# Relay.net
KiCad netlist of a schematic drawn in Altium Designer
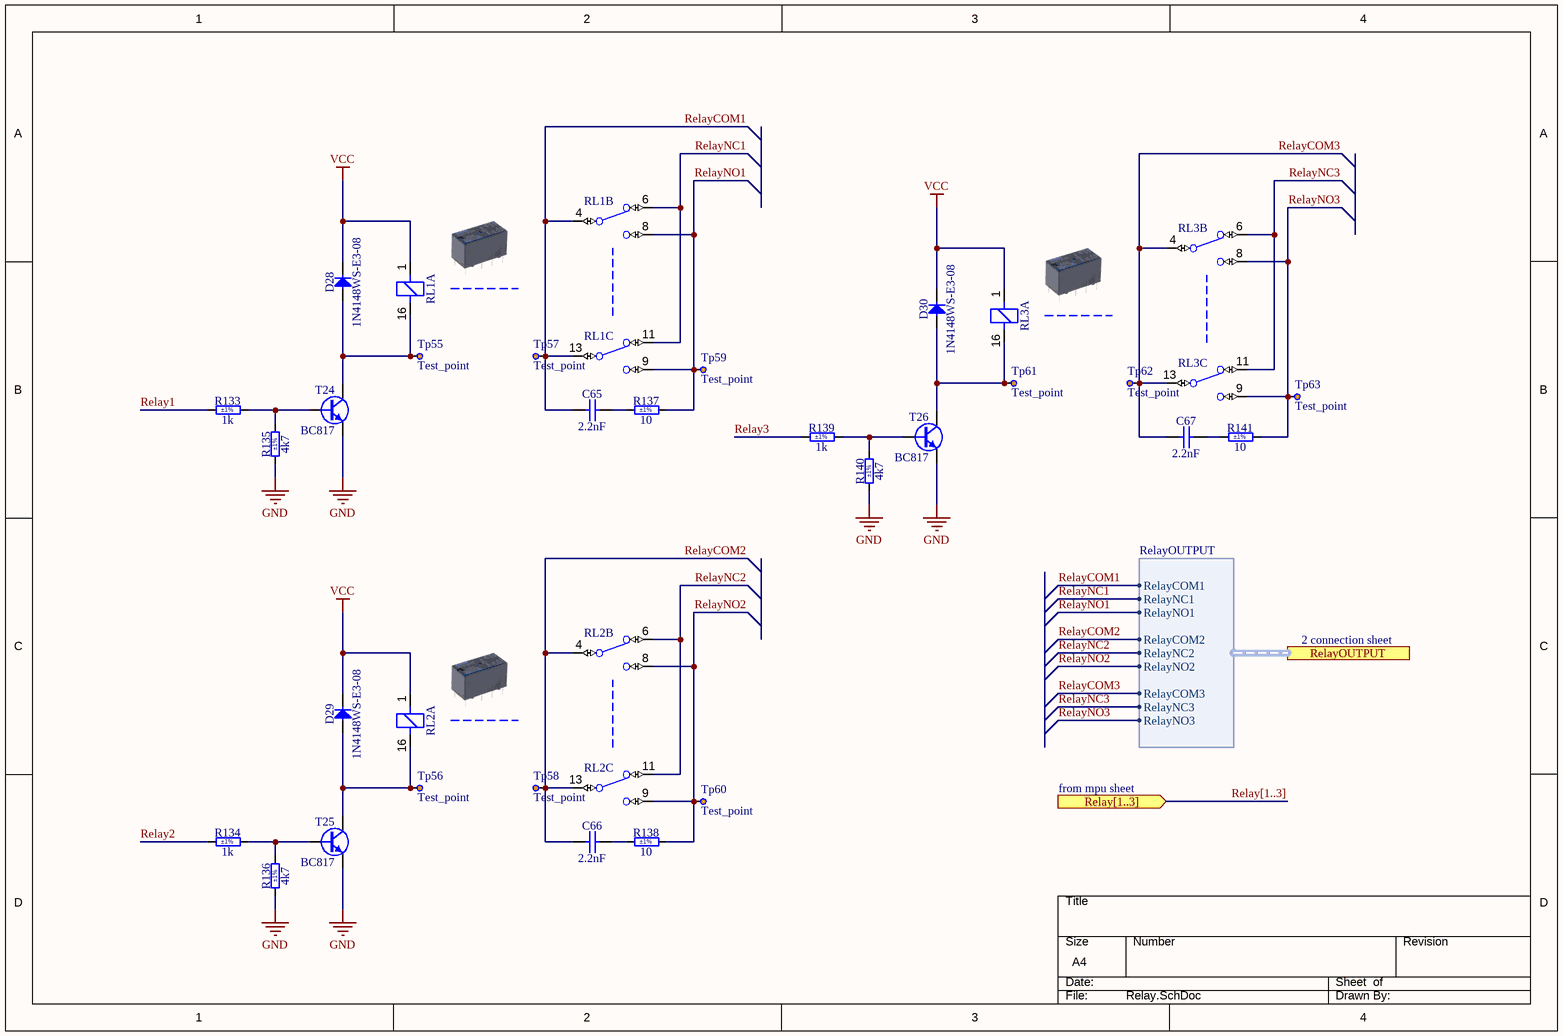
[diagram p0: Relay.SchDoc]

(export (version "E")
  (design (tool "Eeschema 10.0.6"))
  (components
    (comp (ref "C65")
      (value "2.2nF")
      (footprint "CAPRB_MURATA_DE2E3KY222MA2BM01F")
      (description "Non-polarised capacitor")
      (fields
        (field (name "PART NUMBER") "CCR_2.2NF_250V_20%_MURATA_DE2E3KY222MA2BM01F")
        (field (name "VOLTAGE") "250VAC")
        (field (name "AUTHOR") "CERN DEM JLC")
      )
      (libsource (lib "Capacitors") (part "Capacitor - non polarized"))
    )
    (comp (ref "C66")
      (value "2.2nF")
      (footprint "CAPRB_MURATA_DE2E3KY222MA2BM01F")
      (description "Non-polarised capacitor")
      (fields
        (field (name "PART NUMBER") "CCR_2.2NF_250V_20%_MURATA_DE2E3KY222MA2BM01F")
        (field (name "VOLTAGE") "250VAC")
        (field (name "AUTHOR") "CERN DEM JLC")
      )
      (libsource (lib "Capacitors") (part "Capacitor - non polarized"))
    )
    (comp (ref "C67")
      (value "2.2nF")
      (footprint "CAPRB_MURATA_DE2E3KY222MA2BM01F")
      (description "Non-polarised capacitor")
      (fields
        (field (name "PART NUMBER") "CCR_2.2NF_250V_20%_MURATA_DE2E3KY222MA2BM01F")
        (field (name "VOLTAGE") "250VAC")
        (field (name "AUTHOR") "CERN DEM JLC")
      )
      (libsource (lib "Capacitors") (part "Capacitor - non polarized"))
    )
    (comp (ref "D28")
      (value "1N4148WS-E3-08")
      (footprint "SOD2713X115N")
      (description "Diode")
      (fields
        (field (name "VOLTAGE") "75V")
        (field (name "POWER") "150mA")
        (field (name "AUTHOR") "CERN DEM JLC")
      )
      (libsource (lib "ICs And Semiconductors") (part "Diode"))
    )
    (comp (ref "D29")
      (value "1N4148WS-E3-08")
      (footprint "SOD2713X115N")
      (description "Diode")
      (fields
        (field (name "VOLTAGE") "75V")
        (field (name "POWER") "150mA")
        (field (name "AUTHOR") "CERN DEM JLC")
      )
      (libsource (lib "ICs And Semiconductors") (part "Diode"))
    )
    (comp (ref "D30")
      (value "1N4148WS-E3-08")
      (footprint "SOD2713X115N")
      (description "Diode")
      (fields
        (field (name "VOLTAGE") "75V")
        (field (name "POWER") "150mA")
        (field (name "AUTHOR") "CERN DEM JLC")
      )
      (libsource (lib "ICs And Semiconductors") (part "Diode"))
    )
    (comp (ref "R133")
      (value "1k")
      (footprint "RESC1608X55N")
      (description "Resistor - 1%")
      (fields
        (field (name "TOLERANCE") "±1%")
        (field (name "PART NUMBER") "R0603_1K_1%_0.1W_100PPM")
        (field (name "POWER") "0.1W")
        (field (name "AUTHOR") "CERN DEM JLC")
      )
      (libsource (lib "Resistors") (part "Resistor - 1%"))
    )
    (comp (ref "R134")
      (value "1k")
      (footprint "RESC1608X55N")
      (description "Resistor - 1%")
      (fields
        (field (name "TOLERANCE") "±1%")
        (field (name "PART NUMBER") "R0603_1K_1%_0.1W_100PPM")
        (field (name "POWER") "0.1W")
        (field (name "AUTHOR") "CERN DEM JLC")
      )
      (libsource (lib "Resistors") (part "Resistor - 1%"))
    )
    (comp (ref "R135")
      (value "4k7")
      (footprint "RESC1608X55N")
      (description "Resistor - 1%")
      (fields
        (field (name "TOLERANCE") "±1%")
        (field (name "PART NUMBER") "R0603_4K7_1%_0.1W_100PPM")
        (field (name "POWER") "0.1W")
        (field (name "AUTHOR") "CERN DEM JLC")
      )
      (libsource (lib "Resistors") (part "Resistor - 1%"))
    )
    (comp (ref "R136")
      (value "4k7")
      (footprint "RESC1608X55N")
      (description "Resistor - 1%")
      (fields
        (field (name "TOLERANCE") "±1%")
        (field (name "PART NUMBER") "R0603_4K7_1%_0.1W_100PPM")
        (field (name "POWER") "0.1W")
        (field (name "AUTHOR") "CERN DEM JLC")
      )
      (libsource (lib "Resistors") (part "Resistor - 1%"))
    )
    (comp (ref "R137")
      (value "10")
      (footprint "RESC3216X65N")
      (description "Resistor - 1%")
      (fields
        (field (name "TOLERANCE") "±1%")
        (field (name "PART NUMBER") "R1206_10R_1%_0.25W_100PPM")
        (field (name "POWER") "0.25W")
        (field (name "AUTHOR") "CERN DEM BC")
      )
      (libsource (lib "Resistors") (part "Resistor - 1%"))
    )
    (comp (ref "R138")
      (value "10")
      (footprint "RESC3216X65N")
      (description "Resistor - 1%")
      (fields
        (field (name "TOLERANCE") "±1%")
        (field (name "PART NUMBER") "R1206_10R_1%_0.25W_100PPM")
        (field (name "POWER") "0.25W")
        (field (name "AUTHOR") "CERN DEM BC")
      )
      (libsource (lib "Resistors") (part "Resistor - 1%"))
    )
    (comp (ref "R139")
      (value "1k")
      (footprint "RESC1608X55N")
      (description "Resistor - 1%")
      (fields
        (field (name "TOLERANCE") "±1%")
        (field (name "PART NUMBER") "R0603_1K_1%_0.1W_100PPM")
        (field (name "POWER") "0.1W")
        (field (name "AUTHOR") "CERN DEM JLC")
      )
      (libsource (lib "Resistors") (part "Resistor - 1%"))
    )
    (comp (ref "R140")
      (value "4k7")
      (footprint "RESC1608X55N")
      (description "Resistor - 1%")
      (fields
        (field (name "TOLERANCE") "±1%")
        (field (name "PART NUMBER") "R0603_4K7_1%_0.1W_100PPM")
        (field (name "POWER") "0.1W")
        (field (name "AUTHOR") "CERN DEM JLC")
      )
      (libsource (lib "Resistors") (part "Resistor - 1%"))
    )
    (comp (ref "R141")
      (value "10")
      (footprint "RESC3216X65N")
      (description "Resistor - 1%")
      (fields
        (field (name "TOLERANCE") "±1%")
        (field (name "PART NUMBER") "R1206_10R_1%_0.25W_100PPM")
        (field (name "POWER") "0.25W")
        (field (name "AUTHOR") "CERN DEM BC")
      )
      (libsource (lib "Resistors") (part "Resistor - 1%"))
    )
    (comp (ref "RL1")
      (value "REL_OMRON_G5V-2")
      (footprint "REL_OMRON_G5V-2")
      (description "Miniature Relay for Signal Circuits")
      (fields
        (field (name "PART NUMBER") "REL_OMRON_G5V-2-H1 24VDC")
        (field (name "MANUFACTURER") "OMRON ELECTRONIC")
        (field (name "AUTHOR") "CERN DEM JLC")
      )
      (libsource (lib "Eletro-mechanical") (part "REL_OMRON_G5V-2"))
    )
    (comp (ref "RL2")
      (value "REL_OMRON_G5V-2")
      (footprint "REL_OMRON_G5V-2")
      (description "Miniature Relay for Signal Circuits")
      (fields
        (field (name "PART NUMBER") "REL_OMRON_G5V-2-H1 24VDC")
        (field (name "MANUFACTURER") "OMRON ELECTRONIC")
        (field (name "AUTHOR") "CERN DEM JLC")
      )
      (libsource (lib "") (part "REL_OMRON_G5V-2_1"))
    )
    (comp (ref "RL3")
      (value "REL_OMRON_G5V-2")
      (footprint "REL_OMRON_G5V-2")
      (description "Miniature Relay for Signal Circuits")
      (fields
        (field (name "PART NUMBER") "REL_OMRON_G5V-2-H1 24VDC")
        (field (name "MANUFACTURER") "OMRON ELECTRONIC")
        (field (name "AUTHOR") "CERN DEM JLC")
      )
      (libsource (lib "Eletro-mechanical") (part "REL_OMRON_G5V-2"))
    )
    (comp (ref "T24")
      (value "BC817")
      (footprint "SOT95P230X110-3N")
      (description "NPN Transistor")
      (fields (field (name "MANUFACTURER") "NXP SEMICONDUCTORS") (field (name "AUTHOR") "CERN DEM JLC"))
      (libsource (lib "ICs And Semiconductors") (part "NPN B1 E2 C3"))
    )
    (comp (ref "T25")
      (value "BC817")
      (footprint "SOT95P230X110-3N")
      (description "NPN Transistor")
      (fields (field (name "MANUFACTURER") "NXP SEMICONDUCTORS") (field (name "AUTHOR") "CERN DEM JLC"))
      (libsource (lib "ICs And Semiconductors") (part "NPN B1 E2 C3"))
    )
    (comp (ref "T26")
      (value "BC817")
      (footprint "SOT95P230X110-3N")
      (description "NPN Transistor")
      (fields (field (name "MANUFACTURER") "NXP SEMICONDUCTORS") (field (name "AUTHOR") "CERN DEM JLC"))
      (libsource (lib "ICs And Semiconductors") (part "NPN B1 E2 C3"))
    )
    (comp (ref "Tp55")
      (value "Test_point")
      (footprint "fromST:TP_C40")
      (description "Test point")
      (fields (field (name "PUBLISHER") "Altium Limited"))
      (libsource (lib "Sajad_Altium_Library") (part "Test point"))
    )
    (comp (ref "Tp56")
      (value "Test_point")
      (footprint "fromST:TP_C40")
      (description "Test point")
      (fields (field (name "PUBLISHER") "Altium Limited"))
      (libsource (lib "Sajad_Altium_Library") (part "Test point"))
    )
    (comp (ref "Tp57")
      (value "Test_point")
      (footprint "fromST:TP_C40")
      (description "Test point")
      (fields (field (name "PUBLISHER") "Altium Limited"))
      (libsource (lib "Sajad_Altium_Library") (part "Test point"))
    )
    (comp (ref "Tp58")
      (value "Test_point")
      (footprint "fromST:TP_C40")
      (description "Test point")
      (fields (field (name "PUBLISHER") "Altium Limited"))
      (libsource (lib "Sajad_Altium_Library") (part "Test point"))
    )
    (comp (ref "Tp59")
      (value "Test_point")
      (footprint "fromST:TP_C40")
      (description "Test point")
      (fields (field (name "PUBLISHER") "Altium Limited"))
      (libsource (lib "Sajad_Altium_Library") (part "Test point"))
    )
    (comp (ref "Tp60")
      (value "Test_point")
      (footprint "fromST:TP_C40")
      (description "Test point")
      (fields (field (name "PUBLISHER") "Altium Limited"))
      (libsource (lib "Sajad_Altium_Library") (part "Test point"))
    )
    (comp (ref "Tp61")
      (value "Test_point")
      (footprint "fromST:TP_C40")
      (description "Test point")
      (fields (field (name "PUBLISHER") "Altium Limited"))
      (libsource (lib "Sajad_Altium_Library") (part "Test point"))
    )
    (comp (ref "Tp62")
      (value "Test_point")
      (footprint "fromST:TP_C40")
      (description "Test point")
      (fields (field (name "PUBLISHER") "Altium Limited"))
      (libsource (lib "Sajad_Altium_Library") (part "Test point"))
    )
    (comp (ref "Tp63")
      (value "Test_point")
      (footprint "fromST:TP_C40")
      (description "Test point")
      (fields (field (name "PUBLISHER") "Altium Limited"))
      (libsource (lib "Sajad_Altium_Library") (part "Test point"))
    )
  )
  (nets
    (net (code "2") (name "/Relay1") (class "Default")
      (node (ref "R133") (pin "1") (pinfunction "1_1") (pintype "passive"))
    )
    (net (code "3") (name "/Relay2") (class "Default")
      (node (ref "R134") (pin "1") (pinfunction "1_1") (pintype "passive"))
    )
    (net (code "4") (name "/Relay3") (class "Default")
      (node (ref "R139") (pin "1") (pinfunction "1_1") (pintype "passive"))
    )
    (net (code "5") (name "/RelayCOM1") (class "Default")
      (node (ref "C65") (pin "1") (pinfunction "1_1") (pintype "passive"))
      (node (ref "RL1") (pin "13") (pinfunction "C_13") (pintype "bidirectional"))
      (node (ref "RL1") (pin "4") (pinfunction "C_4") (pintype "bidirectional"))
      (node (ref "Tp57") (pin "1") (pinfunction "1_1") (pintype "passive"))
    )
    (net (code "6") (name "/RelayCOM2") (class "Default")
      (node (ref "C66") (pin "1") (pinfunction "1_1") (pintype "passive"))
      (node (ref "RL2") (pin "13") (pinfunction "C_13") (pintype "bidirectional"))
      (node (ref "RL2") (pin "4") (pinfunction "C_4") (pintype "bidirectional"))
      (node (ref "Tp58") (pin "1") (pinfunction "1_1") (pintype "passive"))
    )
    (net (code "7") (name "/RelayCOM3") (class "Default")
      (node (ref "C67") (pin "1") (pinfunction "1_1") (pintype "passive"))
      (node (ref "RL3") (pin "13") (pinfunction "C_13") (pintype "bidirectional"))
      (node (ref "RL3") (pin "4") (pinfunction "C_4") (pintype "bidirectional"))
      (node (ref "Tp62") (pin "1") (pinfunction "1_1") (pintype "passive"))
    )
    (net (code "8") (name "/RelayNC1") (class "Default")
      (node (ref "RL1") (pin "11") (pinfunction "NC_11") (pintype "bidirectional"))
      (node (ref "RL1") (pin "6") (pinfunction "NC_6") (pintype "bidirectional"))
    )
    (net (code "9") (name "/RelayNC2") (class "Default")
      (node (ref "RL2") (pin "11") (pinfunction "NC_11") (pintype "bidirectional"))
      (node (ref "RL2") (pin "6") (pinfunction "NC_6") (pintype "bidirectional"))
    )
    (net (code "10") (name "/RelayNC3") (class "Default")
      (node (ref "RL3") (pin "11") (pinfunction "NC_11") (pintype "bidirectional"))
      (node (ref "RL3") (pin "6") (pinfunction "NC_6") (pintype "bidirectional"))
    )
    (net (code "11") (name "/RelayNO1") (class "Default")
      (node (ref "R137") (pin "2") (pinfunction "2_2") (pintype "passive"))
      (node (ref "RL1") (pin "8") (pinfunction "NO_8") (pintype "bidirectional"))
      (node (ref "RL1") (pin "9") (pinfunction "NO_9") (pintype "bidirectional"))
      (node (ref "Tp59") (pin "1") (pinfunction "1_1") (pintype "passive"))
    )
    (net (code "12") (name "/RelayNO2") (class "Default")
      (node (ref "R138") (pin "2") (pinfunction "2_2") (pintype "passive"))
      (node (ref "RL2") (pin "8") (pinfunction "NO_8") (pintype "bidirectional"))
      (node (ref "RL2") (pin "9") (pinfunction "NO_9") (pintype "bidirectional"))
      (node (ref "Tp60") (pin "1") (pinfunction "1_1") (pintype "passive"))
    )
    (net (code "13") (name "/RelayNO3") (class "Default")
      (node (ref "R141") (pin "2") (pinfunction "2_2") (pintype "passive"))
      (node (ref "RL3") (pin "8") (pinfunction "NO_8") (pintype "bidirectional"))
      (node (ref "RL3") (pin "9") (pinfunction "NO_9") (pintype "bidirectional"))
      (node (ref "Tp63") (pin "1") (pinfunction "1_1") (pintype "passive"))
    )
    (net (code "16") (name "GND") (class "Default")
      (node (ref "R135") (pin "1") (pinfunction "1_1") (pintype "passive"))
      (node (ref "R136") (pin "1") (pinfunction "1_1") (pintype "passive"))
      (node (ref "R140") (pin "1") (pinfunction "1_1") (pintype "passive"))
      (node (ref "T24") (pin "2") (pinfunction "E_2") (pintype "passive"))
      (node (ref "T25") (pin "2") (pinfunction "E_2") (pintype "passive"))
      (node (ref "T26") (pin "2") (pinfunction "E_2") (pintype "passive"))
    )
    (net (code "17") (name "Net-(C65-Pad2)") (class "Default")
      (node (ref "C65") (pin "2") (pinfunction "2_2") (pintype "passive"))
      (node (ref "R137") (pin "1") (pinfunction "1_1") (pintype "passive"))
    )
    (net (code "18") (name "Net-(C66-Pad2)") (class "Default")
      (node (ref "C66") (pin "2") (pinfunction "2_2") (pintype "passive"))
      (node (ref "R138") (pin "1") (pinfunction "1_1") (pintype "passive"))
    )
    (net (code "19") (name "Net-(C67-Pad2)") (class "Default")
      (node (ref "C67") (pin "2") (pinfunction "2_2") (pintype "passive"))
      (node (ref "R141") (pin "1") (pinfunction "1_1") (pintype "passive"))
    )
    (net (code "20") (name "Net-(D28-A)") (class "Default")
      (node (ref "D28") (pin "2") (pinfunction "A_2") (pintype "passive"))
      (node (ref "RL1") (pin "16") (pinfunction "16_16") (pintype "passive"))
      (node (ref "T24") (pin "3") (pinfunction "C_3") (pintype "passive"))
      (node (ref "Tp55") (pin "1") (pinfunction "1_1") (pintype "passive"))
    )
    (net (code "21") (name "Net-(D29-A)") (class "Default")
      (node (ref "D29") (pin "2") (pinfunction "A_2") (pintype "passive"))
      (node (ref "RL2") (pin "16") (pinfunction "16_16") (pintype "passive"))
      (node (ref "T25") (pin "3") (pinfunction "C_3") (pintype "passive"))
      (node (ref "Tp56") (pin "1") (pinfunction "1_1") (pintype "passive"))
    )
    (net (code "22") (name "Net-(D30-A)") (class "Default")
      (node (ref "D30") (pin "2") (pinfunction "A_2") (pintype "passive"))
      (node (ref "RL3") (pin "16") (pinfunction "16_16") (pintype "passive"))
      (node (ref "T26") (pin "3") (pinfunction "C_3") (pintype "passive"))
      (node (ref "Tp61") (pin "1") (pinfunction "1_1") (pintype "passive"))
    )
    (net (code "23") (name "Net-(T24-B)") (class "Default")
      (node (ref "R133") (pin "2") (pinfunction "2_2") (pintype "passive"))
      (node (ref "R135") (pin "2") (pinfunction "2_2") (pintype "passive"))
      (node (ref "T24") (pin "1") (pinfunction "B_1") (pintype "passive"))
    )
    (net (code "24") (name "Net-(T25-B)") (class "Default")
      (node (ref "R134") (pin "2") (pinfunction "2_2") (pintype "passive"))
      (node (ref "R136") (pin "2") (pinfunction "2_2") (pintype "passive"))
      (node (ref "T25") (pin "1") (pinfunction "B_1") (pintype "passive"))
    )
    (net (code "25") (name "Net-(T26-B)") (class "Default")
      (node (ref "R139") (pin "2") (pinfunction "2_2") (pintype "passive"))
      (node (ref "R140") (pin "2") (pinfunction "2_2") (pintype "passive"))
      (node (ref "T26") (pin "1") (pinfunction "B_1") (pintype "passive"))
    )
    (net (code "26") (name "VCC") (class "Default")
      (node (ref "D28") (pin "1") (pinfunction "C_1") (pintype "passive"))
      (node (ref "D29") (pin "1") (pinfunction "C_1") (pintype "passive"))
      (node (ref "D30") (pin "1") (pinfunction "C_1") (pintype "passive"))
      (node (ref "RL1") (pin "1") (pinfunction "1_1") (pintype "passive"))
      (node (ref "RL2") (pin "1") (pinfunction "1_1") (pintype "passive"))
      (node (ref "RL3") (pin "1") (pinfunction "1_1") (pintype "passive"))
    )
  )
)
